# WiFiRadio_r1b3.net
KiCad netlist of a schematic drawn in EAGLE
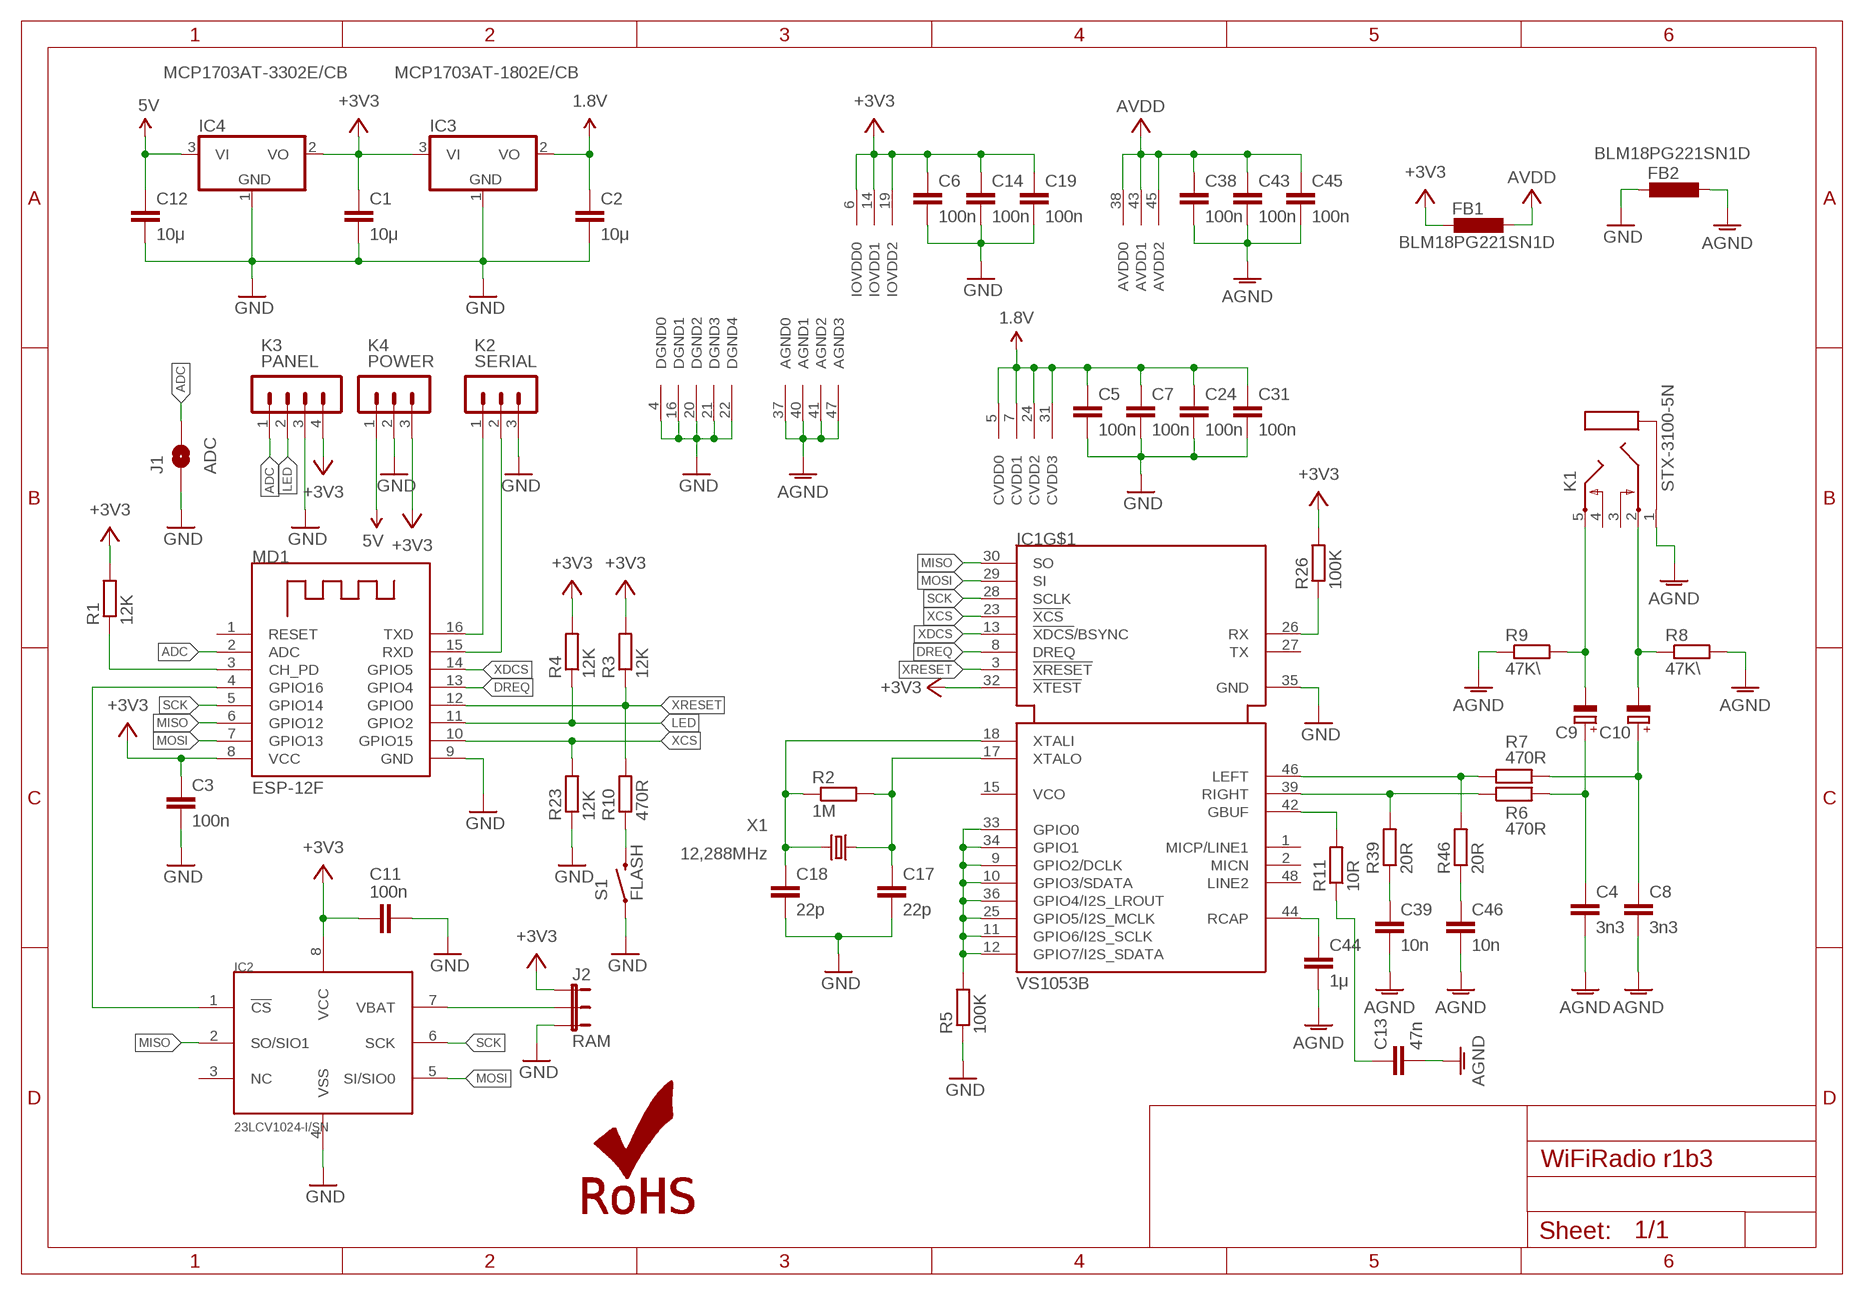
[diagram p0: schematic, sheet 1]

(export (version "E")
  (design (tool "Eeschema 10.0.6"))
  (components
    (comp (ref "C1")
      (value "10μ")
      (footprint "eagle-import:C0805")
      (libsource (lib "eagle-import") (part "C-EUC0805"))
    )
    (comp (ref "C2")
      (value "10μ")
      (footprint "eagle-import:C0805")
      (libsource (lib "eagle-import") (part "C-EUC0805"))
    )
    (comp (ref "C3")
      (value "100n")
      (footprint "eagle-import:C0603")
      (libsource (lib "eagle-import") (part "C-EUC0603"))
    )
    (comp (ref "C4")
      (value "3n3")
      (footprint "eagle-import:C0805")
      (libsource (lib "eagle-import") (part "C-EUC0805"))
    )
    (comp (ref "C5")
      (value "100n")
      (footprint "eagle-import:C0603")
      (libsource (lib "eagle-import") (part "C-EUC0603"))
    )
    (comp (ref "C6")
      (value "100n")
      (footprint "eagle-import:C0603")
      (libsource (lib "eagle-import") (part "C-EUC0603"))
    )
    (comp (ref "C7")
      (value "100n")
      (footprint "eagle-import:C0603")
      (libsource (lib "eagle-import") (part "C-EUC0603"))
    )
    (comp (ref "C8")
      (value "3n3")
      (footprint "eagle-import:C0805")
      (libsource (lib "eagle-import") (part "C-EUC0805"))
    )
    (comp (ref "C9")
      (value "CPOL-EUE3.5-8")
      (footprint "eagle-import:E3,5-8")
      (libsource (lib "eagle-import") (part "CPOL-EUE3.5-8"))
    )
    (comp (ref "C10")
      (value "CPOL-EUE3.5-8")
      (footprint "eagle-import:E3,5-8")
      (libsource (lib "eagle-import") (part "CPOL-EUE3.5-8"))
    )
    (comp (ref "C11")
      (value "100n")
      (footprint "eagle-import:C0603")
      (libsource (lib "eagle-import") (part "C-EUC0603"))
    )
    (comp (ref "C12")
      (value "10μ")
      (footprint "eagle-import:C0805")
      (libsource (lib "eagle-import") (part "C-EUC0805"))
    )
    (comp (ref "C13")
      (value "47n")
      (footprint "eagle-import:C0805")
      (libsource (lib "eagle-import") (part "C-EUC0805"))
    )
    (comp (ref "C14")
      (value "100n")
      (footprint "eagle-import:C0603")
      (libsource (lib "eagle-import") (part "C-EUC0603"))
    )
    (comp (ref "C17")
      (value "22p")
      (footprint "eagle-import:C0805")
      (libsource (lib "eagle-import") (part "C-EUC0805"))
    )
    (comp (ref "C18")
      (value "22p")
      (footprint "eagle-import:C0805")
      (libsource (lib "eagle-import") (part "C-EUC0805"))
    )
    (comp (ref "C19")
      (value "100n")
      (footprint "eagle-import:C0603")
      (libsource (lib "eagle-import") (part "C-EUC0603"))
    )
    (comp (ref "C24")
      (value "100n")
      (footprint "eagle-import:C0603")
      (libsource (lib "eagle-import") (part "C-EUC0603"))
    )
    (comp (ref "C31")
      (value "100n")
      (footprint "eagle-import:C0603")
      (libsource (lib "eagle-import") (part "C-EUC0603"))
    )
    (comp (ref "C38")
      (value "100n")
      (footprint "eagle-import:C0603")
      (libsource (lib "eagle-import") (part "C-EUC0603"))
    )
    (comp (ref "C39")
      (value "10n")
      (footprint "eagle-import:C0805")
      (libsource (lib "eagle-import") (part "C-EUC0805"))
    )
    (comp (ref "C43")
      (value "100n")
      (footprint "eagle-import:C0603")
      (libsource (lib "eagle-import") (part "C-EUC0603"))
    )
    (comp (ref "C44")
      (value "1μ")
      (footprint "eagle-import:C0805")
      (libsource (lib "eagle-import") (part "C-EUC0805"))
    )
    (comp (ref "C45")
      (value "100n")
      (footprint "eagle-import:C0603")
      (libsource (lib "eagle-import") (part "C-EUC0603"))
    )
    (comp (ref "C46")
      (value "10n")
      (footprint "eagle-import:C0805")
      (libsource (lib "eagle-import") (part "C-EUC0805"))
    )
    (comp (ref "FB1")
      (value "BLM18PG221SN1D")
      (footprint "eagle-import:L2012C")
      (libsource (lib "eagle-import") (part "L-EUL2012C"))
    )
    (comp (ref "FB2")
      (value "BLM18PG221SN1D")
      (footprint "eagle-import:L2012C")
      (libsource (lib "eagle-import") (part "L-EUL2012C"))
    )
    (comp (ref "IC1")
      (value "VS1053B")
      (footprint "eagle-import:LQFP48")
      (libsource (lib "eagle-import") (part "VS1053B"))
    )
    (comp (ref "IC2")
      (value "23LCV1024-I/SN")
      (footprint "eagle-import:SO-08")
      (libsource (lib "eagle-import") (part "23LCV1024-I/SN"))
    )
    (comp (ref "IC3")
      (value "MCP1703AT-1802E/CB")
      (footprint "eagle-import:SOT23")
      (libsource (lib "eagle-import") (part "MCP1703CB"))
    )
    (comp (ref "IC4")
      (value "MCP1703AT-3302E/CB")
      (footprint "eagle-import:SOT23")
      (libsource (lib "eagle-import") (part "MCP1703CB"))
    )
    (comp (ref "J1")
      (value "ADC")
      (footprint "eagle-import:SJ_2S")
      (libsource (lib "eagle-import") (part "SOLDERJUMPER-OLDNC"))
    )
    (comp (ref "J2")
      (value "RAM")
      (footprint "eagle-import:SJ_3")
      (libsource (lib "eagle-import") (part "JUMPER-3SMD"))
    )
    (comp (ref "K1")
      (value "STX-3100-5N")
      (footprint "eagle-import:STX3100")
      (libsource (lib "eagle-import") (part "STEREOJACK"))
    )
    (comp (ref "K2")
      (value "SERIAL")
      (footprint "eagle-import:MA03-1")
      (libsource (lib "eagle-import") (part "MA03-1"))
    )
    (comp (ref "K3")
      (value "PANEL")
      (footprint "eagle-import:MA04-1")
      (libsource (lib "eagle-import") (part "MA04-1"))
    )
    (comp (ref "K4")
      (value "POWER")
      (footprint "eagle-import:MA03-1")
      (libsource (lib "eagle-import") (part "MA03-1"))
    )
    (comp (ref "MD1")
      (value "ESP-12F")
      (footprint "eagle-import:ESP-12F")
      (libsource (lib "eagle-import") (part "ESP-12F"))
    )
    (comp (ref "R1")
      (value "12K")
      (footprint "eagle-import:R0805")
      (libsource (lib "eagle-import") (part "R-EU_R0805"))
    )
    (comp (ref "R2")
      (value "1M")
      (footprint "eagle-import:R0805")
      (libsource (lib "eagle-import") (part "R-EU_R0805"))
    )
    (comp (ref "R3")
      (value "12K")
      (footprint "eagle-import:R0805")
      (libsource (lib "eagle-import") (part "R-EU_R0805"))
    )
    (comp (ref "R4")
      (value "12K")
      (footprint "eagle-import:R0805")
      (libsource (lib "eagle-import") (part "R-EU_R0805"))
    )
    (comp (ref "R5")
      (value "100K")
      (footprint "eagle-import:R0805")
      (libsource (lib "eagle-import") (part "R-EU_R0805"))
    )
    (comp (ref "R6")
      (value "470R")
      (footprint "eagle-import:R0805")
      (libsource (lib "eagle-import") (part "R-EU_R0805"))
    )
    (comp (ref "R7")
      (value "470R")
      (footprint "eagle-import:R0805")
      (libsource (lib "eagle-import") (part "R-EU_R0805"))
    )
    (comp (ref "R8")
      (value "47K\\")
      (footprint "eagle-import:R0805")
      (libsource (lib "eagle-import") (part "R-EU_R0805"))
    )
    (comp (ref "R9")
      (value "47K\\")
      (footprint "eagle-import:R0805")
      (libsource (lib "eagle-import") (part "R-EU_R0805"))
    )
    (comp (ref "R10")
      (value "470R")
      (footprint "eagle-import:R0805")
      (libsource (lib "eagle-import") (part "R-EU_R0805"))
    )
    (comp (ref "R11")
      (value "10R")
      (footprint "eagle-import:R0805")
      (libsource (lib "eagle-import") (part "R-EU_R0805"))
    )
    (comp (ref "R23")
      (value "12K")
      (footprint "eagle-import:R0805")
      (libsource (lib "eagle-import") (part "R-EU_R0805"))
    )
    (comp (ref "R26")
      (value "100K")
      (footprint "eagle-import:R0805")
      (libsource (lib "eagle-import") (part "R-EU_R0805"))
    )
    (comp (ref "R39")
      (value "20R")
      (footprint "eagle-import:R0805")
      (libsource (lib "eagle-import") (part "R-EU_R0805"))
    )
    (comp (ref "R46")
      (value "20R")
      (footprint "eagle-import:R0805")
      (libsource (lib "eagle-import") (part "R-EU_R0805"))
    )
    (comp (ref "S1")
      (value "FLASH")
      (footprint "eagle-import:TACTILE-SWITCH-SMD")
      (libsource (lib "eagle-import") (part "SWITCH-MOMENTARY-2SMD"))
    )
    (comp (ref "U$1")
      (value "ROHS_LOGO")
      (footprint "eagle-import:ROHS_LOGO_0.18_IN")
      (libsource (lib "eagle-import") (part "ROHS_LOGO"))
    )
    (comp (ref "X1")
      (value "12,288MHz")
      (footprint "eagle-import:HC49_S")
      (libsource (lib "eagle-import") (part "CRYSTALHC49S"))
    )
  )
  (nets
    (net (code "1") (name "+3V3") (class "Default")
      (node (ref "C1") (pin "1") (pinfunction "1_1") (pintype "passive"))
      (node (ref "C11") (pin "1") (pinfunction "1_1") (pintype "passive"))
      (node (ref "C14") (pin "1") (pinfunction "1_1") (pintype "passive"))
      (node (ref "C19") (pin "1") (pinfunction "1_1") (pintype "passive"))
      (node (ref "C3") (pin "1") (pinfunction "1_1") (pintype "passive"))
      (node (ref "C6") (pin "1") (pinfunction "1_1") (pintype "passive"))
      (node (ref "FB1") (pin "2") (pinfunction "2_2") (pintype "passive"))
      (node (ref "IC1") (pin "14") (pinfunction "IOVDD1_14") (pintype "power_in"))
      (node (ref "IC1") (pin "19") (pinfunction "IOVDD2_19") (pintype "power_in"))
      (node (ref "IC1") (pin "32") (pinfunction "~{XTEST}_32") (pintype "input"))
      (node (ref "IC1") (pin "6") (pinfunction "IOVDD0_6") (pintype "power_in"))
      (node (ref "IC2") (pin "8") (pinfunction "VCC_8") (pintype "power_in"))
      (node (ref "IC3") (pin "3") (pinfunction "VI_3") (pintype "input"))
      (node (ref "IC4") (pin "2") (pinfunction "VO_2") (pintype "passive"))
      (node (ref "J2") (pin "1") (pinfunction "1_1") (pintype "passive"))
      (node (ref "K3") (pin "4") (pinfunction "4_4") (pintype "passive"))
      (node (ref "K4") (pin "3") (pinfunction "3_3") (pintype "passive"))
      (node (ref "MD1") (pin "8") (pinfunction "VCC_8") (pintype "power_in"))
      (node (ref "R1") (pin "2") (pinfunction "2_2") (pintype "passive"))
      (node (ref "R26") (pin "2") (pinfunction "2_2") (pintype "passive"))
      (node (ref "R3") (pin "2") (pinfunction "2_2") (pintype "passive"))
      (node (ref "R4") (pin "2") (pinfunction "2_2") (pintype "passive"))
    )
    (net (code "2") (name "1.8V") (class "Default")
      (node (ref "C2") (pin "1") (pinfunction "1_1") (pintype "passive"))
      (node (ref "C24") (pin "1") (pinfunction "1_1") (pintype "passive"))
      (node (ref "C31") (pin "1") (pinfunction "1_1") (pintype "passive"))
      (node (ref "C5") (pin "1") (pinfunction "1_1") (pintype "passive"))
      (node (ref "C7") (pin "1") (pinfunction "1_1") (pintype "passive"))
      (node (ref "IC1") (pin "24") (pinfunction "CVDD2_24") (pintype "power_in"))
      (node (ref "IC1") (pin "31") (pinfunction "CVDD3_31") (pintype "power_in"))
      (node (ref "IC1") (pin "5") (pinfunction "CVDD0_5") (pintype "power_in"))
      (node (ref "IC1") (pin "7") (pinfunction "CVDD1_7") (pintype "power_in"))
      (node (ref "IC3") (pin "2") (pinfunction "VO_2") (pintype "passive"))
    )
    (net (code "3") (name "5V") (class "Default")
      (node (ref "C12") (pin "1") (pinfunction "1_1") (pintype "passive"))
      (node (ref "IC4") (pin "3") (pinfunction "VI_3") (pintype "input"))
      (node (ref "K4") (pin "1") (pinfunction "1_1") (pintype "passive"))
    )
    (net (code "4") (name "ADC") (class "Default")
      (node (ref "J1") (pin "2") (pinfunction "2_2") (pintype "passive"))
      (node (ref "K3") (pin "1") (pinfunction "1_1") (pintype "passive"))
      (node (ref "MD1") (pin "2") (pinfunction "ADC_2") (pintype "passive"))
    )
    (net (code "5") (name "AGND") (class "Default")
      (node (ref "C13") (pin "2") (pinfunction "2_2") (pintype "passive"))
      (node (ref "C38") (pin "2") (pinfunction "2_2") (pintype "passive"))
      (node (ref "C39") (pin "2") (pinfunction "2_2") (pintype "passive"))
      (node (ref "C4") (pin "2") (pinfunction "2_2") (pintype "passive"))
      (node (ref "C43") (pin "2") (pinfunction "2_2") (pintype "passive"))
      (node (ref "C44") (pin "2") (pinfunction "2_2") (pintype "passive"))
      (node (ref "C45") (pin "2") (pinfunction "2_2") (pintype "passive"))
      (node (ref "C46") (pin "2") (pinfunction "2_2") (pintype "passive"))
      (node (ref "C8") (pin "2") (pinfunction "2_2") (pintype "passive"))
      (node (ref "FB2") (pin "1") (pinfunction "1_1") (pintype "passive"))
      (node (ref "IC1") (pin "37") (pinfunction "AGND0_37") (pintype "power_in"))
      (node (ref "IC1") (pin "40") (pinfunction "AGND1_40") (pintype "power_in"))
      (node (ref "IC1") (pin "41") (pinfunction "AGND2_41") (pintype "power_in"))
      (node (ref "IC1") (pin "47") (pinfunction "AGND3_47") (pintype "power_in"))
      (node (ref "K1") (pin "1") (pinfunction "1_1") (pintype "passive"))
      (node (ref "R8") (pin "2") (pinfunction "2_2") (pintype "passive"))
      (node (ref "R9") (pin "1") (pinfunction "1_1") (pintype "passive"))
    )
    (net (code "6") (name "AVDD") (class "Default")
      (node (ref "C38") (pin "1") (pinfunction "1_1") (pintype "passive"))
      (node (ref "C43") (pin "1") (pinfunction "1_1") (pintype "passive"))
      (node (ref "C45") (pin "1") (pinfunction "1_1") (pintype "passive"))
      (node (ref "FB1") (pin "1") (pinfunction "1_1") (pintype "passive"))
      (node (ref "IC1") (pin "38") (pinfunction "AVDD0_38") (pintype "power_in"))
      (node (ref "IC1") (pin "43") (pinfunction "AVDD1_43") (pintype "power_in"))
      (node (ref "IC1") (pin "45") (pinfunction "AVDD2_45") (pintype "power_in"))
    )
    (net (code "7") (name "DREQ") (class "Default")
      (node (ref "IC1") (pin "8") (pinfunction "DREQ_8") (pintype "output"))
      (node (ref "MD1") (pin "13") (pinfunction "GPIO4_13") (pintype "bidirectional"))
    )
    (net (code "8") (name "GND") (class "Default")
      (node (ref "C1") (pin "2") (pinfunction "2_2") (pintype "passive"))
      (node (ref "C11") (pin "2") (pinfunction "2_2") (pintype "passive"))
      (node (ref "C12") (pin "2") (pinfunction "2_2") (pintype "passive"))
      (node (ref "C14") (pin "2") (pinfunction "2_2") (pintype "passive"))
      (node (ref "C17") (pin "2") (pinfunction "2_2") (pintype "passive"))
      (node (ref "C18") (pin "2") (pinfunction "2_2") (pintype "passive"))
      (node (ref "C19") (pin "2") (pinfunction "2_2") (pintype "passive"))
      (node (ref "C2") (pin "2") (pinfunction "2_2") (pintype "passive"))
      (node (ref "C24") (pin "2") (pinfunction "2_2") (pintype "passive"))
      (node (ref "C3") (pin "2") (pinfunction "2_2") (pintype "passive"))
      (node (ref "C31") (pin "2") (pinfunction "2_2") (pintype "passive"))
      (node (ref "C5") (pin "2") (pinfunction "2_2") (pintype "passive"))
      (node (ref "C6") (pin "2") (pinfunction "2_2") (pintype "passive"))
      (node (ref "C7") (pin "2") (pinfunction "2_2") (pintype "passive"))
      (node (ref "FB2") (pin "2") (pinfunction "2_2") (pintype "passive"))
      (node (ref "IC1") (pin "16") (pinfunction "DGND1_16") (pintype "power_in"))
      (node (ref "IC1") (pin "20") (pinfunction "DGND2_20") (pintype "power_in"))
      (node (ref "IC1") (pin "21") (pinfunction "DGND3_21") (pintype "power_in"))
      (node (ref "IC1") (pin "22") (pinfunction "DGND4_22") (pintype "power_in"))
      (node (ref "IC1") (pin "35") (pinfunction "GND_35") (pintype "power_in"))
      (node (ref "IC1") (pin "4") (pinfunction "DGND0_4") (pintype "power_in"))
      (node (ref "IC2") (pin "4") (pinfunction "VSS_4") (pintype "power_in"))
      (node (ref "IC3") (pin "1") (pinfunction "GND_1") (pintype "passive"))
      (node (ref "IC4") (pin "1") (pinfunction "GND_1") (pintype "passive"))
      (node (ref "J1") (pin "1") (pinfunction "1_1") (pintype "passive"))
      (node (ref "J2") (pin "3") (pinfunction "3_3") (pintype "passive"))
      (node (ref "K2") (pin "3") (pinfunction "3_3") (pintype "passive"))
      (node (ref "K3") (pin "3") (pinfunction "3_3") (pintype "passive"))
      (node (ref "K4") (pin "2") (pinfunction "2_2") (pintype "passive"))
      (node (ref "MD1") (pin "9") (pinfunction "GND_9") (pintype "power_in"))
      (node (ref "R23") (pin "1") (pinfunction "1_1") (pintype "passive"))
      (node (ref "R5") (pin "1") (pinfunction "1_1") (pintype "passive"))
      (node (ref "S1") (pin "1") (pinfunction "1_1") (pintype "passive"))
    )
    (net (code "9") (name "LED") (class "Default")
      (node (ref "K3") (pin "2") (pinfunction "2_2") (pintype "passive"))
      (node (ref "MD1") (pin "11") (pinfunction "GPIO2_11") (pintype "bidirectional"))
      (node (ref "R4") (pin "1") (pinfunction "1_1") (pintype "passive"))
    )
    (net (code "10") (name "MISO") (class "Default")
      (node (ref "IC1") (pin "30") (pinfunction "SO_30") (pintype "output"))
      (node (ref "IC2") (pin "2") (pinfunction "SO/SIO1_2") (pintype "bidirectional"))
      (node (ref "MD1") (pin "6") (pinfunction "GPIO12_6") (pintype "bidirectional"))
    )
    (net (code "11") (name "MOSI") (class "Default")
      (node (ref "IC1") (pin "29") (pinfunction "SI_29") (pintype "input"))
      (node (ref "IC2") (pin "5") (pinfunction "SI/SIO0_5") (pintype "bidirectional"))
      (node (ref "MD1") (pin "7") (pinfunction "GPIO13_7") (pintype "bidirectional"))
    )
    (net (code "12") (name "Net-(C4-Pad1)") (class "Default")
      (node (ref "C4") (pin "1") (pinfunction "1_1") (pintype "passive"))
      (node (ref "C9") (pin "+") (pinfunction "+_+") (pintype "passive"))
      (node (ref "R6") (pin "2") (pinfunction "2_2") (pintype "passive"))
    )
    (net (code "13") (name "Net-(C9-Pad-)") (class "Default")
      (node (ref "C9") (pin "-") (pinfunction "-_-") (pintype "passive"))
      (node (ref "K1") (pin "5") (pinfunction "5_5") (pintype "passive"))
      (node (ref "R9") (pin "2") (pinfunction "2_2") (pintype "passive"))
    )
    (net (code "14") (name "Net-(C10-Pad+)") (class "Default")
      (node (ref "C10") (pin "+") (pinfunction "+_+") (pintype "passive"))
      (node (ref "C8") (pin "1") (pinfunction "1_1") (pintype "passive"))
      (node (ref "R7") (pin "2") (pinfunction "2_2") (pintype "passive"))
    )
    (net (code "15") (name "Net-(C10-Pad-)") (class "Default")
      (node (ref "C10") (pin "-") (pinfunction "-_-") (pintype "passive"))
      (node (ref "K1") (pin "2") (pinfunction "2_2") (pintype "passive"))
      (node (ref "R8") (pin "1") (pinfunction "1_1") (pintype "passive"))
    )
    (net (code "16") (name "Net-(C13-Pad1)") (class "Default")
      (node (ref "C13") (pin "1") (pinfunction "1_1") (pintype "passive"))
      (node (ref "R11") (pin "1") (pinfunction "1_1") (pintype "passive"))
    )
    (net (code "17") (name "Net-(C39-Pad1)") (class "Default")
      (node (ref "C39") (pin "1") (pinfunction "1_1") (pintype "passive"))
      (node (ref "R39") (pin "1") (pinfunction "1_1") (pintype "passive"))
    )
    (net (code "18") (name "Net-(C46-Pad1)") (class "Default")
      (node (ref "C46") (pin "1") (pinfunction "1_1") (pintype "passive"))
      (node (ref "R46") (pin "1") (pinfunction "1_1") (pintype "passive"))
    )
    (net (code "19") (name "Net-(IC1A-GBUF)") (class "Default")
      (node (ref "IC1") (pin "42") (pinfunction "GBUF_42") (pintype "output"))
      (node (ref "R11") (pin "2") (pinfunction "2_2") (pintype "passive"))
    )
    (net (code "20") (name "Net-(IC1A-GPIO0)") (class "Default")
      (node (ref "IC1") (pin "10") (pinfunction "GPIO3/SDATA_10") (pintype "bidirectional"))
      (node (ref "IC1") (pin "11") (pinfunction "GPIO6/I2S_SCLK_11") (pintype "bidirectional"))
      (node (ref "IC1") (pin "12") (pinfunction "GPIO7/I2S_SDATA_12") (pintype "bidirectional"))
      (node (ref "IC1") (pin "25") (pinfunction "GPIO5/I2S_MCLK_25") (pintype "bidirectional"))
      (node (ref "IC1") (pin "33") (pinfunction "GPIO0_33") (pintype "bidirectional"))
      (node (ref "IC1") (pin "34") (pinfunction "GPIO1_34") (pintype "bidirectional"))
      (node (ref "IC1") (pin "36") (pinfunction "GPIO4/I2S_LROUT_36") (pintype "bidirectional"))
      (node (ref "IC1") (pin "9") (pinfunction "GPIO2/DCLK_9") (pintype "bidirectional"))
      (node (ref "R5") (pin "2") (pinfunction "2_2") (pintype "passive"))
    )
    (net (code "21") (name "Net-(IC1A-LEFT)") (class "Default")
      (node (ref "IC1") (pin "46") (pinfunction "LEFT_46") (pintype "output"))
      (node (ref "R46") (pin "2") (pinfunction "2_2") (pintype "passive"))
      (node (ref "R7") (pin "1") (pinfunction "1_1") (pintype "passive"))
    )
    (net (code "22") (name "Net-(IC1A-RCAP)") (class "Default")
      (node (ref "C44") (pin "1") (pinfunction "1_1") (pintype "passive"))
      (node (ref "IC1") (pin "44") (pinfunction "RCAP_44") (pintype "bidirectional"))
    )
    (net (code "23") (name "Net-(IC1A-RIGHT)") (class "Default")
      (node (ref "IC1") (pin "39") (pinfunction "RIGHT_39") (pintype "output"))
      (node (ref "R39") (pin "2") (pinfunction "2_2") (pintype "passive"))
      (node (ref "R6") (pin "1") (pinfunction "1_1") (pintype "passive"))
    )
    (net (code "24") (name "Net-(IC1A-RX)") (class "Default")
      (node (ref "IC1") (pin "26") (pinfunction "RX_26") (pintype "input"))
      (node (ref "R26") (pin "1") (pinfunction "1_1") (pintype "passive"))
    )
    (net (code "25") (name "Net-(IC1A-XTALI)") (class "Default")
      (node (ref "C18") (pin "1") (pinfunction "1_1") (pintype "passive"))
      (node (ref "IC1") (pin "18") (pinfunction "XTALI_18") (pintype "input"))
      (node (ref "R2") (pin "1") (pinfunction "1_1") (pintype "passive"))
      (node (ref "X1") (pin "2") (pinfunction "2_2") (pintype "passive"))
    )
    (net (code "26") (name "Net-(IC1A-XTALO)") (class "Default")
      (node (ref "C17") (pin "1") (pinfunction "1_1") (pintype "passive"))
      (node (ref "IC1") (pin "17") (pinfunction "XTALO_17") (pintype "output"))
      (node (ref "R2") (pin "2") (pinfunction "2_2") (pintype "passive"))
      (node (ref "X1") (pin "1") (pinfunction "1_1") (pintype "passive"))
    )
    (net (code "27") (name "Net-(IC2-VBAT)") (class "Default")
      (node (ref "IC2") (pin "7") (pinfunction "VBAT_7") (pintype "power_in"))
      (node (ref "J2") (pin "2") (pinfunction "2_2") (pintype "passive"))
    )
    (net (code "28") (name "Net-(IC2-~{CS})") (class "Default")
      (node (ref "IC2") (pin "1") (pinfunction "~{CS}_1") (pintype "input"))
      (node (ref "MD1") (pin "4") (pinfunction "GPIO16_4") (pintype "bidirectional"))
    )
    (net (code "29") (name "Net-(MD1-CH_PD)") (class "Default")
      (node (ref "MD1") (pin "3") (pinfunction "CH_PD_3") (pintype "input"))
      (node (ref "R1") (pin "1") (pinfunction "1_1") (pintype "passive"))
    )
    (net (code "30") (name "Net-(MD1-RXD)") (class "Default")
      (node (ref "K2") (pin "2") (pinfunction "2_2") (pintype "passive"))
      (node (ref "MD1") (pin "15") (pinfunction "RXD_15") (pintype "input"))
    )
    (net (code "31") (name "Net-(MD1-TXD)") (class "Default")
      (node (ref "K2") (pin "1") (pinfunction "1_1") (pintype "passive"))
      (node (ref "MD1") (pin "16") (pinfunction "TXD_16") (pintype "output"))
    )
    (net (code "32") (name "Net-(S1-2)") (class "Default")
      (node (ref "R10") (pin "1") (pinfunction "1_1") (pintype "passive"))
      (node (ref "S1") (pin "3") (pinfunction "2_3") (pintype "passive"))
    )
    (net (code "33") (name "SCK") (class "Default")
      (node (ref "IC1") (pin "28") (pinfunction "SCLK_28") (pintype "input"))
      (node (ref "IC2") (pin "6") (pinfunction "SCK_6") (pintype "input"))
      (node (ref "MD1") (pin "5") (pinfunction "GPIO14_5") (pintype "bidirectional"))
    )
    (net (code "34") (name "XCS") (class "Default")
      (node (ref "IC1") (pin "23") (pinfunction "~{XCS}_23") (pintype "input"))
      (node (ref "MD1") (pin "10") (pinfunction "GPIO15_10") (pintype "bidirectional"))
      (node (ref "R23") (pin "2") (pinfunction "2_2") (pintype "passive"))
    )
    (net (code "35") (name "XDCS") (class "Default")
      (node (ref "IC1") (pin "13") (pinfunction "~{XDCS}/BSYNC_13") (pintype "input"))
      (node (ref "MD1") (pin "14") (pinfunction "GPIO5_14") (pintype "bidirectional"))
    )
    (net (code "36") (name "XRESET") (class "Default")
      (node (ref "IC1") (pin "3") (pinfunction "~{XRESET}_3") (pintype "input"))
      (node (ref "MD1") (pin "12") (pinfunction "GPIO0_12") (pintype "bidirectional"))
      (node (ref "R10") (pin "2") (pinfunction "2_2") (pintype "passive"))
      (node (ref "R3") (pin "1") (pinfunction "1_1") (pintype "passive"))
    )
    (net (code "37") (name "unconnected-(IC1A-LINE2-Pad48)") (class "Default")
      (node (ref "IC1") (pin "48") (pinfunction "LINE2_48") (pintype "input"))
    )
    (net (code "38") (name "unconnected-(IC1A-MICN-Pad2)") (class "Default")
      (node (ref "IC1") (pin "2") (pinfunction "MICN_2") (pintype "input"))
    )
    (net (code "39") (name "unconnected-(IC1A-MICP{slash}LINE1-Pad1)") (class "Default")
      (node (ref "IC1") (pin "1") (pinfunction "MICP/LINE1_1") (pintype "input"))
    )
    (net (code "40") (name "unconnected-(IC1A-TX-Pad27)") (class "Default")
      (node (ref "IC1") (pin "27") (pinfunction "TX_27") (pintype "output"))
    )
    (net (code "41") (name "unconnected-(IC1A-VCO-Pad15)") (class "Default")
      (node (ref "IC1") (pin "15") (pinfunction "VCO_15") (pintype "output"))
    )
    (net (code "42") (name "unconnected-(IC2-NC-Pad3)") (class "Default")
      (node (ref "IC2") (pin "3") (pinfunction "NC_3") (pintype "no_connect"))
    )
    (net (code "43") (name "unconnected-(K1-Pad3)") (class "Default")
      (node (ref "K1") (pin "3") (pinfunction "3_3") (pintype "passive"))
    )
    (net (code "44") (name "unconnected-(K1-Pad4)") (class "Default")
      (node (ref "K1") (pin "4") (pinfunction "4_4") (pintype "passive"))
    )
    (net (code "45") (name "unconnected-(MD1-RESET-Pad1)") (class "Default")
      (node (ref "MD1") (pin "1") (pinfunction "RESET_1") (pintype "input"))
    )
  )
)
